# Magic_PCB_Pro_Micro.net
KiCad netlist of a schematic drawn in EAGLE
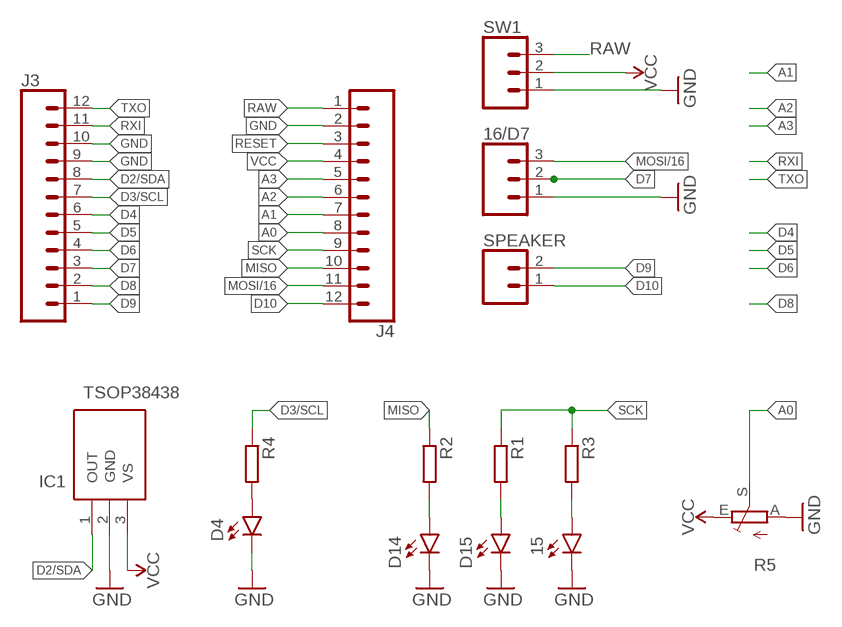
[diagram p0: schematic, sheet 1]

(export (version "E")
  (design (tool "Eeschema 10.0.6"))
  (components
    (comp (ref "15")
      (value "GREEN")
      (footprint "eagle-import:SFH482")
      (libsource (lib "eagle-import") (part "LEDSFH482"))
    )
    (comp (ref "16/D7")
      (value "CONN_03")
      (footprint "eagle-import:1X03")
      (libsource (lib "eagle-import") (part "CONN_03"))
    )
    (comp (ref "D4")
      (value "GREEN")
      (footprint "eagle-import:SFH482")
      (libsource (lib "eagle-import") (part "LEDSFH482"))
    )
    (comp (ref "D14")
      (value "GREEN")
      (footprint "eagle-import:SFH482")
      (libsource (lib "eagle-import") (part "LEDSFH482"))
    )
    (comp (ref "D15")
      (value "Yellow")
      (footprint "eagle-import:SFH482")
      (libsource (lib "eagle-import") (part "LEDSFH482"))
    )
    (comp (ref "IC1")
      (value "TSOP38438")
      (footprint "eagle-import:TSOP38238")
      (fields (field (name "MOUSER_PART_NUMBER") "78-TSOP38438"))
      (libsource (lib "eagle-import") (part "TSOP38438"))
    )
    (comp (ref "J3")
      (value "CONN_12LONGPADS")
      (footprint "eagle-import:1X12_LONGPADS")
      (libsource (lib "eagle-import") (part "CONN_12LONGPADS"))
    )
    (comp (ref "J4")
      (value "CONN_12LONGPADS")
      (footprint "eagle-import:1X12_LONGPADS")
      (libsource (lib "eagle-import") (part "CONN_12LONGPADS"))
    )
    (comp (ref "R1")
      (value "160")
      (footprint "eagle-import:R3216W")
      (libsource (lib "eagle-import") (part "R-EU_R3216W"))
    )
    (comp (ref "R2")
      (value "160")
      (footprint "eagle-import:R3216W")
      (libsource (lib "eagle-import") (part "R-EU_R3216W"))
    )
    (comp (ref "R3")
      (value "160")
      (footprint "eagle-import:R3216W")
      (libsource (lib "eagle-import") (part "R-EU_R3216W"))
    )
    (comp (ref "R4")
      (value "68")
      (footprint "eagle-import:R3216W")
      (libsource (lib "eagle-import") (part "R-EU_R3216W"))
    )
    (comp (ref "R5")
      (value "TRIM_EU-S64W")
      (footprint "eagle-import:S64W")
      (libsource (lib "eagle-import") (part "TRIM_EU-S64W"))
    )
    (comp (ref "SPEAKER")
      (value "CONN_02")
      (footprint "eagle-import:1X02")
      (libsource (lib "eagle-import") (part "CONN_02"))
    )
    (comp (ref "SW1")
      (value "CONN_03")
      (footprint "eagle-import:1X03")
      (libsource (lib "eagle-import") (part "CONN_03"))
    )
  )
  (nets
    (net (code "1") (name "A0") (class "Default")
      (node (ref "J4") (pin "8") (pinfunction "8_8") (pintype "passive"))
      (node (ref "R5") (pin "S") (pinfunction "S_S") (pintype "passive"))
    )
    (net (code "2") (name "A1") (class "Default")
      (node (ref "J4") (pin "7") (pinfunction "7_7") (pintype "passive"))
    )
    (net (code "3") (name "A2") (class "Default")
      (node (ref "J4") (pin "6") (pinfunction "6_6") (pintype "passive"))
    )
    (net (code "4") (name "A3") (class "Default")
      (node (ref "J4") (pin "5") (pinfunction "5_5") (pintype "passive"))
    )
    (net (code "5") (name "D2{slash}SDA") (class "Default")
      (node (ref "IC1") (pin "1") (pinfunction "OUT_1") (pintype "bidirectional"))
      (node (ref "J3") (pin "8") (pinfunction "8_8") (pintype "passive"))
    )
    (net (code "6") (name "D3{slash}SCL") (class "Default")
      (node (ref "J3") (pin "7") (pinfunction "7_7") (pintype "passive"))
      (node (ref "R4") (pin "1") (pinfunction "1_1") (pintype "passive"))
    )
    (net (code "7") (name "D4") (class "Default")
      (node (ref "J3") (pin "6") (pinfunction "6_6") (pintype "passive"))
    )
    (net (code "8") (name "D5") (class "Default")
      (node (ref "J3") (pin "5") (pinfunction "5_5") (pintype "passive"))
    )
    (net (code "9") (name "D6") (class "Default")
      (node (ref "J3") (pin "4") (pinfunction "4_4") (pintype "passive"))
    )
    (net (code "10") (name "D7") (class "Default")
      (node (ref "16/D7") (pin "2") (pinfunction "2_2") (pintype "passive"))
      (node (ref "J3") (pin "3") (pinfunction "3_3") (pintype "passive"))
    )
    (net (code "11") (name "D8") (class "Default")
      (node (ref "J3") (pin "2") (pinfunction "2_2") (pintype "passive"))
    )
    (net (code "12") (name "D9") (class "Default")
      (node (ref "J3") (pin "1") (pinfunction "1_1") (pintype "passive"))
      (node (ref "SPEAKER") (pin "2") (pinfunction "2_2") (pintype "passive"))
    )
    (net (code "13") (name "D10") (class "Default")
      (node (ref "J4") (pin "12") (pinfunction "12_12") (pintype "passive"))
      (node (ref "SPEAKER") (pin "1") (pinfunction "1_1") (pintype "passive"))
    )
    (net (code "14") (name "GND") (class "Default")
      (node (ref "15") (pin "K") (pinfunction "C_K") (pintype "passive"))
      (node (ref "16/D7") (pin "1") (pinfunction "1_1") (pintype "passive"))
      (node (ref "D14") (pin "K") (pinfunction "C_K") (pintype "passive"))
      (node (ref "D15") (pin "K") (pinfunction "C_K") (pintype "passive"))
      (node (ref "D4") (pin "K") (pinfunction "C_K") (pintype "passive"))
      (node (ref "IC1") (pin "2") (pinfunction "GND_2") (pintype "bidirectional"))
      (node (ref "J3") (pin "10") (pinfunction "10_10") (pintype "passive"))
      (node (ref "J3") (pin "9") (pinfunction "9_9") (pintype "passive"))
      (node (ref "J4") (pin "2") (pinfunction "2_2") (pintype "passive"))
      (node (ref "R5") (pin "A") (pinfunction "A_A") (pintype "passive"))
      (node (ref "SW1") (pin "1") (pinfunction "1_1") (pintype "passive"))
    )
    (net (code "15") (name "MISO") (class "Default")
      (node (ref "J4") (pin "10") (pinfunction "10_10") (pintype "passive"))
      (node (ref "R2") (pin "1") (pinfunction "1_1") (pintype "passive"))
    )
    (net (code "16") (name "MOSI{slash}16") (class "Default")
      (node (ref "16/D7") (pin "3") (pinfunction "3_3") (pintype "passive"))
      (node (ref "J4") (pin "11") (pinfunction "11_11") (pintype "passive"))
    )
    (net (code "17") (name "Net-(15-PadA)") (class "Default")
      (node (ref "15") (pin "A") (pinfunction "A_A") (pintype "passive"))
      (node (ref "R3") (pin "2") (pinfunction "2_2") (pintype "passive"))
    )
    (net (code "18") (name "Net-(D4-PadA)") (class "Default")
      (node (ref "D4") (pin "A") (pinfunction "A_A") (pintype "passive"))
      (node (ref "R4") (pin "2") (pinfunction "2_2") (pintype "passive"))
    )
    (net (code "19") (name "Net-(D14-PadA)") (class "Default")
      (node (ref "D14") (pin "A") (pinfunction "A_A") (pintype "passive"))
      (node (ref "R2") (pin "2") (pinfunction "2_2") (pintype "passive"))
    )
    (net (code "20") (name "Net-(D15-PadA)") (class "Default")
      (node (ref "D15") (pin "A") (pinfunction "A_A") (pintype "passive"))
      (node (ref "R1") (pin "2") (pinfunction "2_2") (pintype "passive"))
    )
    (net (code "21") (name "RAW") (class "Default")
      (node (ref "J4") (pin "1") (pinfunction "1_1") (pintype "passive"))
      (node (ref "SW1") (pin "3") (pinfunction "3_3") (pintype "passive"))
    )
    (net (code "22") (name "RESET") (class "Default")
      (node (ref "J4") (pin "3") (pinfunction "3_3") (pintype "passive"))
    )
    (net (code "23") (name "RXI") (class "Default")
      (node (ref "J3") (pin "11") (pinfunction "11_11") (pintype "passive"))
    )
    (net (code "24") (name "SCK") (class "Default")
      (node (ref "J4") (pin "9") (pinfunction "9_9") (pintype "passive"))
      (node (ref "R1") (pin "1") (pinfunction "1_1") (pintype "passive"))
      (node (ref "R3") (pin "1") (pinfunction "1_1") (pintype "passive"))
    )
    (net (code "25") (name "TXO") (class "Default")
      (node (ref "J3") (pin "12") (pinfunction "12_12") (pintype "passive"))
    )
    (net (code "26") (name "VCC") (class "Default")
      (node (ref "IC1") (pin "3") (pinfunction "VS_3") (pintype "bidirectional"))
      (node (ref "J4") (pin "4") (pinfunction "4_4") (pintype "passive"))
      (node (ref "R5") (pin "E") (pinfunction "E_E") (pintype "passive"))
      (node (ref "SW1") (pin "2") (pinfunction "2_2") (pintype "passive"))
    )
  )
)
